# Gate_Driver.net
KiCad netlist of a schematic drawn in Altium Designer
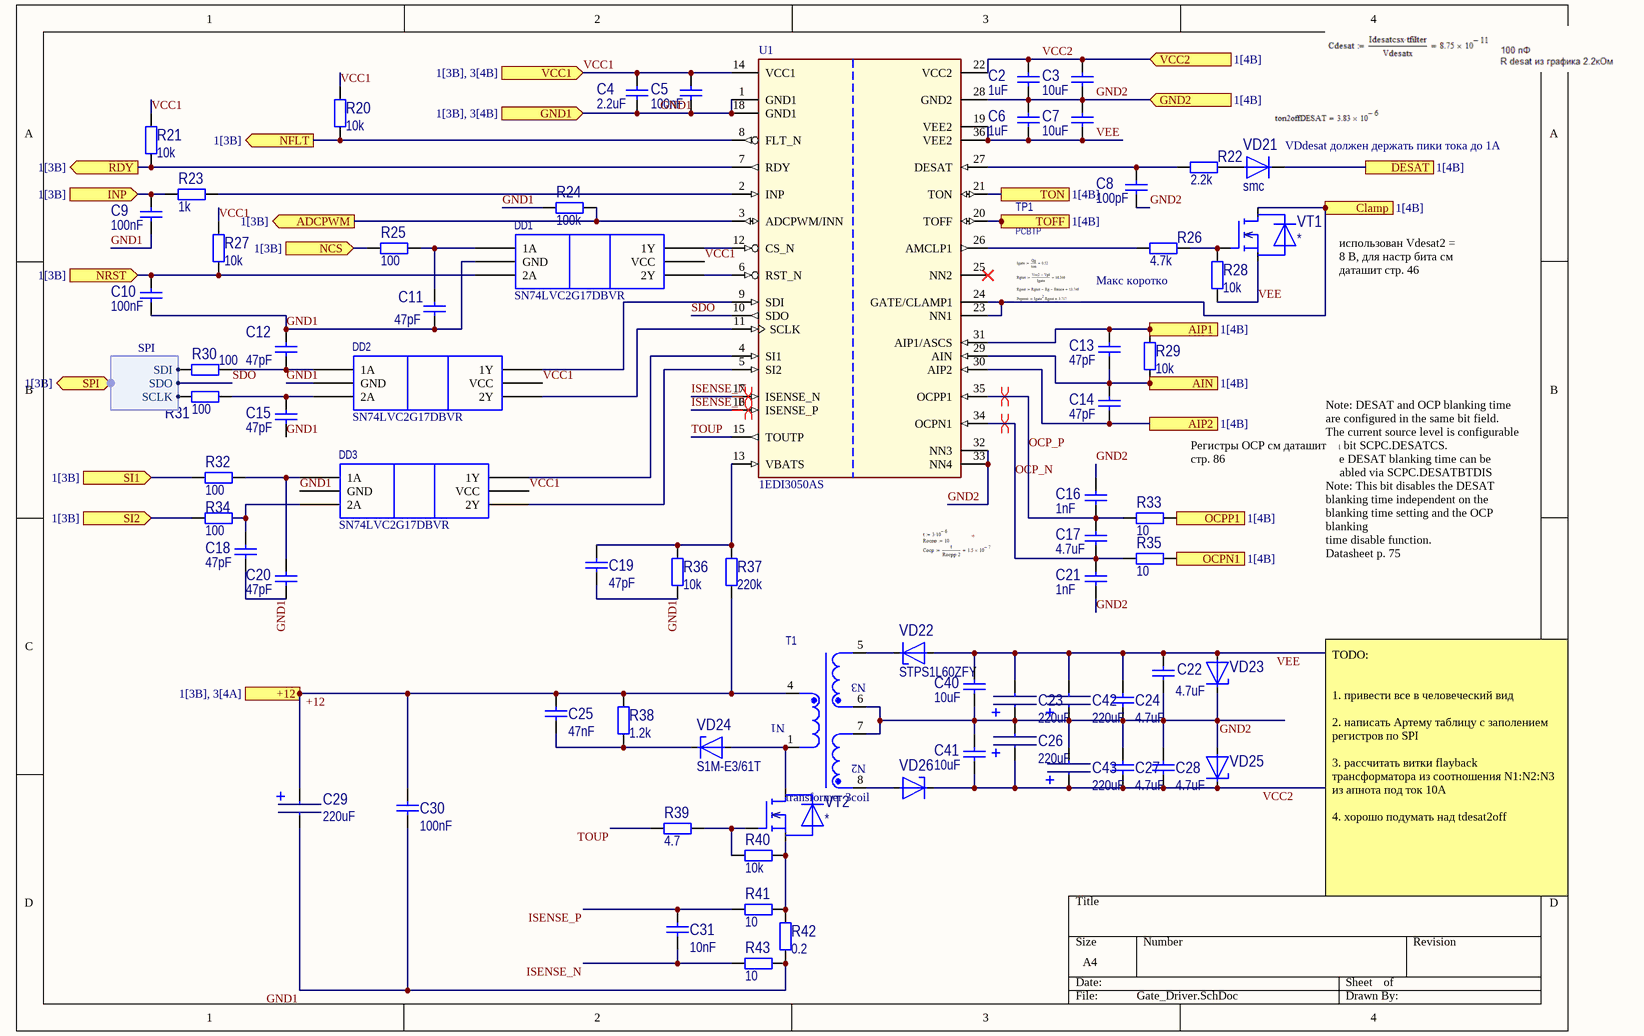
[diagram p0: Gate_Driver.SchDoc]

(export (version "E")
  (design (tool "Eeschema 10.0.6"))
  (components
    (comp (ref "C2")
      (value "1uF")
      (footprint "6332[2512]")
      (description "Конденсатор")
      (fields
        (field (name "MANUFACTURER") "Murata")
        (field (name "MANUFACTURERPARTNUMBER") "GRM21B X7R 104 50V")
      )
      (libsource (lib "Schlibgost") (part "C-4del"))
    )
    (comp (ref "C3")
      (value "10uF")
      (footprint "6332[2512]")
      (description "Конденсатор")
      (fields
        (field (name "MANUFACTURER") "Murata")
        (field (name "MANUFACTURERPARTNUMBER") "GRM21B X7R 104 50V")
      )
      (libsource (lib "Schlibgost") (part "C-4del"))
    )
    (comp (ref "C4")
      (value "2.2uF")
      (footprint "3216[1206]")
      (description "Конденсатор")
      (fields
        (field (name "MANUFACTURER") "Murata")
        (field (name "MANUFACTURERPARTNUMBER") "GRM21B X7R 104 50V")
      )
      (libsource (lib "Schlibgost") (part "C-4del"))
    )
    (comp (ref "C5")
      (value "100nF")
      (footprint "2012[0805]")
      (description "Конденсатор")
      (fields
        (field (name "MANUFACTURER") "Murata")
        (field (name "MANUFACTURERPARTNUMBER") "GRM21B X7R 104 50V")
      )
      (libsource (lib "Schlibgost") (part "C-4del"))
    )
    (comp (ref "C6")
      (value "1uF")
      (footprint "6332[2512]")
      (description "Конденсатор")
      (fields
        (field (name "MANUFACTURER") "Murata")
        (field (name "MANUFACTURERPARTNUMBER") "GRM21B X7R 104 50V")
      )
      (libsource (lib "Schlibgost") (part "C-4del"))
    )
    (comp (ref "C7")
      (value "10uF")
      (footprint "6332[2512]")
      (description "Конденсатор")
      (fields
        (field (name "MANUFACTURER") "Murata")
        (field (name "MANUFACTURERPARTNUMBER") "GRM21B X7R 104 50V")
      )
      (libsource (lib "Schlibgost") (part "C-4del"))
    )
    (comp (ref "C8")
      (value "100pF")
      (footprint "2012[0805]")
      (description "Конденсатор")
      (fields
        (field (name "MANUFACTURER") "Murata")
        (field (name "MANUFACTURERPARTNUMBER") "GRM21B X7R 104 50V")
      )
      (libsource (lib "Schlibgost") (part "C-4del"))
    )
    (comp (ref "C9")
      (value "100nF")
      (footprint "2012[0805]")
      (description "Конденсатор")
      (fields
        (field (name "MANUFACTURER") "Murata")
        (field (name "MANUFACTURERPARTNUMBER") "GRM21B X7R 104 50V")
      )
      (libsource (lib "Schlibgost") (part "C-4del"))
    )
    (comp (ref "C10")
      (value "100nF")
      (footprint "2012[0805]")
      (description "Конденсатор")
      (fields
        (field (name "MANUFACTURER") "Murata")
        (field (name "MANUFACTURERPARTNUMBER") "GRM21B X7R 104 50V")
      )
      (libsource (lib "Schlibgost") (part "C-4del"))
    )
    (comp (ref "C11")
      (value "47pF")
      (footprint "2012[0805]")
      (description "Конденсатор")
      (fields
        (field (name "MANUFACTURER") "Murata")
        (field (name "MANUFACTURERPARTNUMBER") "GRM21B X7R 104 50V")
      )
      (libsource (lib "Schlibgost") (part "C-4del"))
    )
    (comp (ref "C12")
      (value "47pF")
      (footprint "2012[0805]")
      (description "Конденсатор")
      (fields
        (field (name "MANUFACTURER") "Murata")
        (field (name "MANUFACTURERPARTNUMBER") "GRM21B X7R 104 50V")
      )
      (libsource (lib "Schlibgost") (part "C-4del"))
    )
    (comp (ref "C13")
      (value "47pF")
      (footprint "2012[0805]")
      (description "Конденсатор")
      (fields
        (field (name "MANUFACTURER") "Murata")
        (field (name "MANUFACTURERPARTNUMBER") "GRM21B X7R 104 50V")
      )
      (libsource (lib "Schlibgost") (part "C-4del"))
    )
    (comp (ref "C14")
      (value "47pF")
      (footprint "2012[0805]")
      (description "Конденсатор")
      (fields
        (field (name "MANUFACTURER") "Murata")
        (field (name "MANUFACTURERPARTNUMBER") "GRM21B X7R 104 50V")
      )
      (libsource (lib "Schlibgost") (part "C-4del"))
    )
    (comp (ref "C15")
      (value "47pF")
      (footprint "2012[0805]")
      (description "Конденсатор")
      (fields
        (field (name "MANUFACTURER") "Murata")
        (field (name "MANUFACTURERPARTNUMBER") "GRM21B X7R 104 50V")
      )
      (libsource (lib "Schlibgost") (part "C-4del"))
    )
    (comp (ref "C16")
      (value "1nF")
      (footprint "2012[0805]")
      (description "Конденсатор")
      (fields
        (field (name "MANUFACTURER") "Murata")
        (field (name "MANUFACTURERPARTNUMBER") "GRM21B X7R 104 50V")
      )
      (libsource (lib "Schlibgost") (part "C-4del"))
    )
    (comp (ref "C17")
      (value "4.7uF")
      (footprint "2012[0805]")
      (description "Конденсатор")
      (fields
        (field (name "MANUFACTURER") "Murata")
        (field (name "MANUFACTURERPARTNUMBER") "GRM21B X7R 104 50V")
      )
      (libsource (lib "Schlibgost") (part "C-4del"))
    )
    (comp (ref "C18")
      (value "47pF")
      (footprint "2012[0805]")
      (description "Конденсатор")
      (fields
        (field (name "MANUFACTURER") "Murata")
        (field (name "MANUFACTURERPARTNUMBER") "GRM21B X7R 104 50V")
      )
      (libsource (lib "Schlibgost") (part "C-4del"))
    )
    (comp (ref "C19")
      (value "47pF")
      (footprint "2012[0805]")
      (description "Конденсатор")
      (fields
        (field (name "MANUFACTURER") "Murata")
        (field (name "MANUFACTURERPARTNUMBER") "GRM21B X7R 104 50V")
      )
      (libsource (lib "Schlibgost") (part "C-4del"))
    )
    (comp (ref "C20")
      (value "47pF")
      (footprint "2012[0805]")
      (description "Конденсатор")
      (fields
        (field (name "MANUFACTURER") "Murata")
        (field (name "MANUFACTURERPARTNUMBER") "GRM21B X7R 104 50V")
      )
      (libsource (lib "Schlibgost") (part "C-4del"))
    )
    (comp (ref "C21")
      (value "1nF")
      (footprint "2012[0805]")
      (description "Конденсатор")
      (fields
        (field (name "MANUFACTURER") "Murata")
        (field (name "MANUFACTURERPARTNUMBER") "GRM21B X7R 104 50V")
      )
      (libsource (lib "Schlibgost") (part "C-4del"))
    )
    (comp (ref "C22")
      (value "4.7uF")
      (footprint "6332[2512]")
      (description "Конденсатор")
      (fields
        (field (name "MANUFACTURER") "Murata")
        (field (name "MANUFACTURERPARTNUMBER") "GRM21B X7R 104 50V")
      )
      (libsource (lib "Schlibgost") (part "C-4del"))
    )
    (comp (ref "C23")
      (value "220uF")
      (footprint "ECAP 220 50V")
      (description "Конденсатор электролитический")
      (libsource (lib "Schlibgost") (part "C pol"))
    )
    (comp (ref "C24")
      (value "4.7uF")
      (footprint "6332[2512]")
      (description "Конденсатор")
      (fields
        (field (name "MANUFACTURER") "Murata")
        (field (name "MANUFACTURERPARTNUMBER") "GRM21B X7R 104 50V")
      )
      (libsource (lib "Schlibgost") (part "C-4del"))
    )
    (comp (ref "C25")
      (value "47nF")
      (footprint "2012[0805]")
      (description "Конденсатор")
      (fields
        (field (name "MANUFACTURER") "Murata")
        (field (name "MANUFACTURERPARTNUMBER") "GRM21B X7R 104 50V")
      )
      (libsource (lib "Schlibgost") (part "C-4del"))
    )
    (comp (ref "C26")
      (value "220uF")
      (footprint "ECAP 220 50V")
      (description "Конденсатор электролитический")
      (libsource (lib "Schlibgost") (part "C pol"))
    )
    (comp (ref "C27")
      (value "4.7uF")
      (footprint "6332[2512]")
      (description "Конденсатор")
      (fields
        (field (name "MANUFACTURER") "Murata")
        (field (name "MANUFACTURERPARTNUMBER") "GRM21B X7R 104 50V")
      )
      (libsource (lib "Schlibgost") (part "C-4del"))
    )
    (comp (ref "C28")
      (value "4.7uF")
      (footprint "6332[2512]")
      (description "Конденсатор")
      (fields
        (field (name "MANUFACTURER") "Murata")
        (field (name "MANUFACTURERPARTNUMBER") "GRM21B X7R 104 50V")
      )
      (libsource (lib "Schlibgost") (part "C-4del"))
    )
    (comp (ref "C29")
      (value "220uF")
      (footprint "A(3216)")
      (description "Конденсатор электролитический")
      (libsource (lib "Schlibgost") (part "C pol"))
    )
    (comp (ref "C30")
      (value "100nF")
      (footprint "6332[2512]")
      (description "Конденсатор")
      (fields
        (field (name "MANUFACTURER") "Murata")
        (field (name "MANUFACTURERPARTNUMBER") "GRM21B X7R 104 50V")
      )
      (libsource (lib "Schlibgost") (part "C-4del"))
    )
    (comp (ref "C31")
      (value "10nF")
      (footprint "1005[0402]")
      (description "Конденсатор")
      (fields
        (field (name "MANUFACTURER") "Murata")
        (field (name "MANUFACTURERPARTNUMBER") "GRM21B X7R 104 50V")
      )
      (libsource (lib "Schlibgost") (part "C-4del"))
    )
    (comp (ref "C40")
      (value "10uF")
      (footprint "6332[2512]")
      (description "Конденсатор")
      (fields
        (field (name "MANUFACTURER") "Murata")
        (field (name "MANUFACTURERPARTNUMBER") "GRM21B X7R 104 50V")
      )
      (libsource (lib "Schlibgost") (part "C-4del"))
    )
    (comp (ref "C41")
      (value "10uF")
      (footprint "6332[2512]")
      (description "Конденсатор")
      (fields
        (field (name "MANUFACTURER") "Murata")
        (field (name "MANUFACTURERPARTNUMBER") "GRM21B X7R 104 50V")
      )
      (libsource (lib "Schlibgost") (part "C-4del"))
    )
    (comp (ref "C42")
      (value "220uF")
      (footprint "ECAP 220 50V")
      (description "Конденсатор электролитический")
      (libsource (lib "Schlibgost") (part "C pol"))
    )
    (comp (ref "C43")
      (value "220uF")
      (footprint "ECAP 220 50V")
      (description "Конденсатор электролитический")
      (libsource (lib "Schlibgost") (part "C pol"))
    )
    (comp (ref "DD1")
      (value "SN74LVC2G17DBVR")
      (footprint "SOT23-6")
      (libsource (lib "Schlibgost_pn") (part "SN74LVC"))
    )
    (comp (ref "DD2")
      (value "SN74LVC2G17DBVR")
      (footprint "SOT23-6")
      (libsource (lib "Schlibgost_pn") (part "SN74LVC"))
    )
    (comp (ref "DD3")
      (value "SN74LVC2G17DBVR")
      (footprint "SOT23-6")
      (libsource (lib "Schlibgost_pn") (part "SN74LVC"))
    )
    (comp (ref "R20")
      (value "10k")
      (footprint "2012[0805]")
      (description "Резистор")
      (fields (field (name "TOLERANCE") "5%") (field (name "MANUFACTURER") "Yageo"))
      (libsource (lib "") (part "R-4del_2"))
    )
    (comp (ref "R21")
      (value "10k")
      (footprint "2012[0805]")
      (description "Резистор")
      (fields (field (name "TOLERANCE") "5%") (field (name "MANUFACTURER") "Yageo"))
      (libsource (lib "") (part "R-4del_2"))
    )
    (comp (ref "R22")
      (value "2.2k")
      (footprint "3216[1206]")
      (description "Резистор")
      (fields (field (name "TOLERANCE") "5%") (field (name "MANUFACTURER") "Yageo"))
      (libsource (lib "") (part "R-4del_1"))
    )
    (comp (ref "R23")
      (value "1k")
      (footprint "2012[0805]")
      (description "Резистор")
      (fields (field (name "TOLERANCE") "5%") (field (name "MANUFACTURER") "Yageo"))
      (libsource (lib "Schlibgost") (part "R-4del"))
    )
    (comp (ref "R24")
      (value "100k")
      (footprint "1005[0402]")
      (description "Резистор")
      (fields (field (name "TOLERANCE") "5%") (field (name "MANUFACTURER") "Yageo"))
      (libsource (lib "Schlibgost") (part "R-4del"))
    )
    (comp (ref "R25")
      (value "100")
      (footprint "2012[0805]")
      (description "Резистор")
      (fields (field (name "TOLERANCE") "5%") (field (name "MANUFACTURER") "Yageo"))
      (libsource (lib "Schlibgost") (part "R-4del"))
    )
    (comp (ref "R26")
      (value "4.7k")
      (footprint "2012[0805]")
      (description "Резистор")
      (fields (field (name "TOLERANCE") "5%") (field (name "MANUFACTURER") "Yageo"))
      (libsource (lib "") (part "R-4del_1"))
    )
    (comp (ref "R27")
      (value "10k")
      (footprint "2012[0805]")
      (description "Резистор")
      (fields (field (name "TOLERANCE") "5%") (field (name "MANUFACTURER") "Yageo"))
      (libsource (lib "") (part "R-4del_2"))
    )
    (comp (ref "R28")
      (value "10k")
      (footprint "2012[0805]")
      (description "Резистор")
      (fields (field (name "TOLERANCE") "5%") (field (name "MANUFACTURER") "Yageo"))
      (libsource (lib "") (part "R-4del_2"))
    )
    (comp (ref "R29")
      (value "10k")
      (footprint "2012[0805]")
      (description "Резистор")
      (fields (field (name "TOLERANCE") "5%") (field (name "MANUFACTURER") "Yageo"))
      (libsource (lib "") (part "R-4del_2"))
    )
    (comp (ref "R30")
      (value "100")
      (footprint "2012[0805]")
      (description "Резистор")
      (fields (field (name "TOLERANCE") "5%") (field (name "MANUFACTURER") "Yageo"))
      (libsource (lib "Schlibgost") (part "R-4del"))
    )
    (comp (ref "R31")
      (value "100")
      (footprint "2012[0805]")
      (description "Резистор")
      (fields (field (name "TOLERANCE") "5%") (field (name "MANUFACTURER") "Yageo"))
      (libsource (lib "Schlibgost") (part "R-4del"))
    )
    (comp (ref "R32")
      (value "100")
      (footprint "2012[0805]")
      (description "Резистор")
      (fields (field (name "TOLERANCE") "5%") (field (name "MANUFACTURER") "Yageo"))
      (libsource (lib "Schlibgost") (part "R-4del"))
    )
    (comp (ref "R33")
      (value "10")
      (footprint "2012[0805]")
      (description "Резистор")
      (fields (field (name "TOLERANCE") "5%") (field (name "MANUFACTURER") "Yageo"))
      (libsource (lib "Schlibgost") (part "R-4del"))
    )
    (comp (ref "R34")
      (value "100")
      (footprint "2012[0805]")
      (description "Резистор")
      (fields (field (name "TOLERANCE") "5%") (field (name "MANUFACTURER") "Yageo"))
      (libsource (lib "Schlibgost") (part "R-4del"))
    )
    (comp (ref "R35")
      (value "10")
      (footprint "2012[0805]")
      (description "Резистор")
      (fields (field (name "TOLERANCE") "5%") (field (name "MANUFACTURER") "Yageo"))
      (libsource (lib "Schlibgost") (part "R-4del"))
    )
    (comp (ref "R36")
      (value "10k")
      (footprint "2012[0805]")
      (description "Резистор")
      (fields (field (name "TOLERANCE") "5%") (field (name "MANUFACTURER") "Yageo"))
      (libsource (lib "") (part "R-4del_2"))
    )
    (comp (ref "R37")
      (value "220k")
      (footprint "2012[0805]")
      (description "Резистор")
      (fields (field (name "TOLERANCE") "5%") (field (name "MANUFACTURER") "Yageo"))
      (libsource (lib "") (part "R-4del_2"))
    )
    (comp (ref "R38")
      (value "1.2k")
      (footprint "2012[0805]")
      (description "Резистор")
      (fields (field (name "TOLERANCE") "5%") (field (name "MANUFACTURER") "Yageo"))
      (libsource (lib "") (part "R-4del_2"))
    )
    (comp (ref "R39")
      (value "4.7")
      (footprint "2012[0805]")
      (description "Резистор")
      (fields (field (name "TOLERANCE") "5%") (field (name "MANUFACTURER") "Yageo"))
      (libsource (lib "") (part "R-4del_1"))
    )
    (comp (ref "R40")
      (value "10k")
      (footprint "2012[0805]")
      (description "Резистор")
      (fields (field (name "TOLERANCE") "5%") (field (name "MANUFACTURER") "Yageo"))
      (libsource (lib "Schlibgost") (part "R-4del"))
    )
    (comp (ref "R41")
      (value "10")
      (footprint "2012[0805]")
      (description "Резистор")
      (fields (field (name "TOLERANCE") "5%") (field (name "MANUFACTURER") "Yageo"))
      (libsource (lib "Schlibgost") (part "R-4del"))
    )
    (comp (ref "R42")
      (value "0.2")
      (footprint "2512")
      (description "Резистор")
      (fields (field (name "TOLERANCE") "5%") (field (name "MANUFACTURER") "Yageo"))
      (libsource (lib "") (part "R-4del_3"))
    )
    (comp (ref "R43")
      (value "10")
      (footprint "2012[0805]")
      (description "Резистор")
      (fields (field (name "TOLERANCE") "5%") (field (name "MANUFACTURER") "Yageo"))
      (libsource (lib "Schlibgost") (part "R-4del"))
    )
    (comp (ref "T1")
      (value "transformer 3coil")
      (footprint "E 13/7/4")
      (libsource (lib "Schlibgost") (part "transformer 3coil"))
    )
    (comp (ref "TP1") (value "PCBTP") (libsource (lib "Schlibgost") (part "Testpoint")))
    (comp (ref "U1")
      (value "1EDI3050AS")
      (description "Single channel isolated IGBT/SiC-MOSFET driver")
      (fields (field (name "MANUFACTURER") "Infineon Technologies"))
      (libsource (lib "1EDI3050AS") (part "1EDI3050AS"))
    )
    (comp (ref "VD21")
      (value "smc")
      (footprint "SMС")
      (description "Диод")
      (libsource (lib "Schlibgost") (part "VD Diod"))
    )
    (comp (ref "VD22")
      (value "STPS1L60ZFY")
      (footprint "SOD-123")
      (description "Стабилитрон односторонний")
      (libsource (lib "Schlibgost") (part "VD Stabilitron"))
    )
    (comp (ref "VD23")
      (value "~")
      (footprint "SMС")
      (description "Стабилитрон односторонний")
      (libsource (lib "Schlibgost") (part "VD Stabilitron"))
    )
    (comp (ref "VD24")
      (value "S1M-E3/61T")
      (footprint "SMB")
      (description "Стабилитрон односторонний")
      (libsource (lib "Schlibgost") (part "VD Stabilitron"))
    )
    (comp (ref "VD25")
      (value "~")
      (footprint "SMС")
      (description "Стабилитрон односторонний")
      (libsource (lib "Schlibgost") (part "VD Stabilitron"))
    )
    (comp (ref "VD26")
      (value "~")
      (footprint "SOD-123")
      (description "Стабилитрон односторонний")
      (libsource (lib "Schlibgost") (part "VD Stabilitron"))
    )
    (comp (ref "VT1")
      (value "*")
      (description "Транзистор полевой n-канальный")
      (libsource (lib "Schlibgost") (part "VT Transistor NMOS+D"))
    )
    (comp (ref "VT2")
      (value "*")
      (description "Транзистор полевой n-канальный")
      (libsource (lib "Schlibgost") (part "VT Transistor NMOS+D"))
    )
  )
  (nets
    (net (code "2") (name "/+12") (class "Default")
      (node (ref "C25") (pin "1") (pinfunction "1_1") (pintype "passive"))
      (node (ref "C29") (pin "1") (pinfunction "1_1") (pintype "passive"))
      (node (ref "C30") (pin "1") (pinfunction "1_1") (pintype "passive"))
      (node (ref "R37") (pin "1") (pinfunction "1_1") (pintype "passive"))
      (node (ref "R38") (pin "2") (pinfunction "2_2") (pintype "passive"))
      (node (ref "T1") (pin "4") (pinfunction "4_4") (pintype "passive"))
    )
    (net (code "3") (name "/ADCPWM") (class "Default")
      (node (ref "R24") (pin "1") (pinfunction "1_1") (pintype "passive"))
      (node (ref "U1") (pin "3") (pinfunction "ADCPWM/INN_3") (pintype "bidirectional"))
    )
    (net (code "4") (name "/AIN") (class "Default")
      (node (ref "C13") (pin "2") (pinfunction "2_2") (pintype "passive"))
      (node (ref "C14") (pin "1") (pinfunction "1_1") (pintype "passive"))
      (node (ref "R29") (pin "1") (pinfunction "1_1") (pintype "passive"))
      (node (ref "U1") (pin "29") (pinfunction "AIN_29") (pintype "input"))
    )
    (net (code "5") (name "/AIP1") (class "Default")
      (node (ref "C13") (pin "1") (pinfunction "1_1") (pintype "passive"))
      (node (ref "R29") (pin "2") (pinfunction "2_2") (pintype "passive"))
      (node (ref "U1") (pin "31") (pinfunction "AIP1/ASCS_31") (pintype "input"))
    )
    (net (code "6") (name "/AIP2") (class "Default")
      (node (ref "C14") (pin "2") (pinfunction "2_2") (pintype "passive"))
      (node (ref "U1") (pin "30") (pinfunction "AIP2_30") (pintype "input"))
    )
    (net (code "7") (name "/Clamp") (class "Default")
      (node (ref "U1") (pin "23") (pinfunction "NN1_23") (pintype "passive"))
      (node (ref "U1") (pin "24") (pinfunction "GATE/CLAMP1_24") (pintype "power_in"))
      (node (ref "VT1") (pin "1") (pinfunction "D_1") (pintype "passive"))
    )
    (net (code "8") (name "/DESAT") (class "Default")
      (node (ref "VD21") (pin "2") (pinfunction "K_2") (pintype "passive"))
    )
    (net (code "9") (name "/GND1") (class "Default")
      (node (ref "C10") (pin "2") (pinfunction "2_2") (pintype "passive"))
      (node (ref "C11") (pin "2") (pinfunction "2_2") (pintype "passive"))
      (node (ref "C12") (pin "1") (pinfunction "1_1") (pintype "passive"))
      (node (ref "C15") (pin "2") (pinfunction "2_2") (pintype "passive"))
      (node (ref "C18") (pin "2") (pinfunction "2_2") (pintype "passive"))
      (node (ref "C19") (pin "2") (pinfunction "2_2") (pintype "passive"))
      (node (ref "C20") (pin "2") (pinfunction "2_2") (pintype "passive"))
      (node (ref "C29") (pin "2") (pinfunction "2_2") (pintype "passive"))
      (node (ref "C30") (pin "2") (pinfunction "2_2") (pintype "passive"))
      (node (ref "C4") (pin "2") (pinfunction "2_2") (pintype "passive"))
      (node (ref "C5") (pin "2") (pinfunction "2_2") (pintype "passive"))
      (node (ref "C9") (pin "2") (pinfunction "2_2") (pintype "passive"))
      (node (ref "DD1") (pin "2") (pinfunction "GND_2") (pintype "passive"))
      (node (ref "DD2") (pin "2") (pinfunction "GND_2") (pintype "passive"))
      (node (ref "DD3") (pin "2") (pinfunction "GND_2") (pintype "passive"))
      (node (ref "R24") (pin "2") (pinfunction "2_2") (pintype "passive"))
      (node (ref "R36") (pin "1") (pinfunction "1_1") (pintype "passive"))
      (node (ref "R42") (pin "2") (pinfunction "2_2") (pintype "passive"))
      (node (ref "R43") (pin "1") (pinfunction "1_1") (pintype "passive"))
      (node (ref "U1") (pin "1") (pinfunction "GND1_1") (pintype "power_in"))
      (node (ref "U1") (pin "18") (pinfunction "GND1_18") (pintype "power_in"))
    )
    (net (code "10") (name "/GND2") (class "Default")
      (node (ref "C16") (pin "1") (pinfunction "1_1") (pintype "passive"))
      (node (ref "C2") (pin "2") (pinfunction "2_2") (pintype "passive"))
      (node (ref "C21") (pin "2") (pinfunction "2_2") (pintype "passive"))
      (node (ref "C22") (pin "1") (pinfunction "1_1") (pintype "passive"))
      (node (ref "C23") (pin "1") (pinfunction "1_1") (pintype "passive"))
      (node (ref "C24") (pin "1") (pinfunction "1_1") (pintype "passive"))
      (node (ref "C26") (pin "2") (pinfunction "2_2") (pintype "passive"))
      (node (ref "C27") (pin "2") (pinfunction "2_2") (pintype "passive"))
      (node (ref "C28") (pin "2") (pinfunction "2_2") (pintype "passive"))
      (node (ref "C3") (pin "2") (pinfunction "2_2") (pintype "passive"))
      (node (ref "C40") (pin "2") (pinfunction "2_2") (pintype "passive"))
      (node (ref "C41") (pin "1") (pinfunction "1_1") (pintype "passive"))
      (node (ref "C42") (pin "1") (pinfunction "1_1") (pintype "passive"))
      (node (ref "C43") (pin "2") (pinfunction "2_2") (pintype "passive"))
      (node (ref "C6") (pin "1") (pinfunction "1_1") (pintype "passive"))
      (node (ref "C7") (pin "1") (pinfunction "1_1") (pintype "passive"))
      (node (ref "C8") (pin "2") (pinfunction "2_2") (pintype "passive"))
      (node (ref "T1") (pin "6") (pinfunction "6_6") (pintype "passive"))
      (node (ref "T1") (pin "7") (pinfunction "7_7") (pintype "passive"))
      (node (ref "U1") (pin "28") (pinfunction "GND2_28") (pintype "power_in"))
      (node (ref "U1") (pin "32") (pinfunction "NN3_32") (pintype "passive"))
      (node (ref "U1") (pin "33") (pinfunction "NN4_33") (pintype "passive"))
      (node (ref "VD23") (pin "2") (pinfunction "K_2") (pintype "passive"))
      (node (ref "VD25") (pin "1") (pinfunction "A_1") (pintype "passive"))
    )
    (net (code "11") (name "/INP") (class "Default")
      (node (ref "C9") (pin "1") (pinfunction "1_1") (pintype "passive"))
      (node (ref "R23") (pin "2") (pinfunction "2_2") (pintype "passive"))
    )
    (net (code "12") (name "/ISENSE_N") (class "Default")
      (node (ref "C31") (pin "2") (pinfunction "2_2") (pintype "passive"))
      (node (ref "R43") (pin "2") (pinfunction "2_2") (pintype "passive"))
      (node (ref "U1") (pin "17") (pinfunction "ISENSE_N_17") (pintype "input"))
    )
    (net (code "13") (name "/ISENSE_P") (class "Default")
      (node (ref "C31") (pin "1") (pinfunction "1_1") (pintype "passive"))
      (node (ref "R41") (pin "2") (pinfunction "2_2") (pintype "passive"))
      (node (ref "U1") (pin "16") (pinfunction "ISENSE_P_16") (pintype "input"))
    )
    (net (code "14") (name "/NCS") (class "Default")
      (node (ref "R25") (pin "2") (pinfunction "2_2") (pintype "passive"))
    )
    (net (code "15") (name "/NFLT") (class "Default")
      (node (ref "R20") (pin "1") (pinfunction "1_1") (pintype "passive"))
      (node (ref "U1") (pin "8") (pinfunction "FLT_N_8") (pintype "output"))
    )
    (net (code "16") (name "/NRST") (class "Default")
      (node (ref "C10") (pin "1") (pinfunction "1_1") (pintype "passive"))
      (node (ref "DD1") (pin "3") (pinfunction "2A_3") (pintype "passive"))
      (node (ref "R27") (pin "1") (pinfunction "1_1") (pintype "passive"))
    )
    (net (code "17") (name "/OCPN1") (class "Default")
      (node (ref "R35") (pin "1") (pinfunction "1_1") (pintype "passive"))
    )
    (net (code "18") (name "/OCPP1") (class "Default")
      (node (ref "R33") (pin "1") (pinfunction "1_1") (pintype "passive"))
    )
    (net (code "19") (name "/OCP_N") (class "Default")
      (node (ref "C17") (pin "2") (pinfunction "2_2") (pintype "passive"))
      (node (ref "C21") (pin "1") (pinfunction "1_1") (pintype "passive"))
      (node (ref "R35") (pin "2") (pinfunction "2_2") (pintype "passive"))
      (node (ref "U1") (pin "34") (pinfunction "OCPN1_34") (pintype "input"))
    )
    (net (code "20") (name "/OCP_P") (class "Default")
      (node (ref "C16") (pin "2") (pinfunction "2_2") (pintype "passive"))
      (node (ref "C17") (pin "1") (pinfunction "1_1") (pintype "passive"))
      (node (ref "R33") (pin "2") (pinfunction "2_2") (pintype "passive"))
      (node (ref "U1") (pin "35") (pinfunction "OCPP1_35") (pintype "input"))
    )
    (net (code "21") (name "/RDY") (class "Default")
      (node (ref "R21") (pin "1") (pinfunction "1_1") (pintype "passive"))
      (node (ref "U1") (pin "7") (pinfunction "RDY_7") (pintype "output"))
    )
    (net (code "22") (name "/SCLK") (class "Default")
      (node (ref "R31") (pin "2") (pinfunction "2_2") (pintype "passive"))
    )
    (net (code "23") (name "/SDI") (class "Default")
      (node (ref "R30") (pin "2") (pinfunction "2_2") (pintype "passive"))
    )
    (net (code "24") (name "/SDO") (class "Default")
      (node (ref "U1") (pin "10") (pinfunction "SDO_10") (pintype "output"))
    )
    (net (code "25") (name "/SI1") (class "Default")
      (node (ref "R32") (pin "2") (pinfunction "2_2") (pintype "passive"))
    )
    (net (code "26") (name "/SI2") (class "Default")
      (node (ref "R34") (pin "2") (pinfunction "2_2") (pintype "passive"))
    )
    (net (code "27") (name "/TOFF") (class "Default")
      (node (ref "TP1") (pin "1") (pinfunction "1_1") (pintype "passive"))
      (node (ref "U1") (pin "20") (pinfunction "TOFF_20") (pintype "bidirectional"))
    )
    (net (code "28") (name "/TON") (class "Default")
      (node (ref "U1") (pin "21") (pinfunction "TON_21") (pintype "bidirectional"))
    )
    (net (code "29") (name "/TOUP") (class "Default")
      (node (ref "R39") (pin "1") (pinfunction "1_1") (pintype "passive"))
      (node (ref "U1") (pin "15") (pinfunction "TOUTP_15") (pintype "output"))
    )
    (net (code "30") (name "/VCC1") (class "Default")
      (node (ref "C4") (pin "1") (pinfunction "1_1") (pintype "passive"))
      (node (ref "C5") (pin "1") (pinfunction "1_1") (pintype "passive"))
      (node (ref "DD1") (pin "5") (pinfunction "VCC_5") (pintype "passive"))
      (node (ref "DD2") (pin "5") (pinfunction "VCC_5") (pintype "passive"))
      (node (ref "DD3") (pin "5") (pinfunction "VCC_5") (pintype "passive"))
      (node (ref "R20") (pin "2") (pinfunction "2_2") (pintype "passive"))
      (node (ref "R21") (pin "2") (pinfunction "2_2") (pintype "passive"))
      (node (ref "R27") (pin "2") (pinfunction "2_2") (pintype "passive"))
      (node (ref "U1") (pin "14") (pinfunction "VCC1_14") (pintype "power_in"))
    )
    (net (code "31") (name "/VCC2") (class "Default")
      (node (ref "C2") (pin "1") (pinfunction "1_1") (pintype "passive"))
      (node (ref "C26") (pin "1") (pinfunction "1_1") (pintype "passive"))
      (node (ref "C27") (pin "1") (pinfunction "1_1") (pintype "passive"))
      (node (ref "C28") (pin "1") (pinfunction "1_1") (pintype "passive"))
      (node (ref "C3") (pin "1") (pinfunction "1_1") (pintype "passive"))
      (node (ref "C41") (pin "2") (pinfunction "2_2") (pintype "passive"))
      (node (ref "C43") (pin "1") (pinfunction "1_1") (pintype "passive"))
      (node (ref "U1") (pin "22") (pinfunction "VCC2_22") (pintype "power_in"))
      (node (ref "VD25") (pin "2") (pinfunction "K_2") (pintype "passive"))
      (node (ref "VD26") (pin "2") (pinfunction "K_2") (pintype "passive"))
    )
    (net (code "32") (name "/VEE") (class "Default")
      (node (ref "C22") (pin "2") (pinfunction "2_2") (pintype "passive"))
      (node (ref "C23") (pin "2") (pinfunction "2_2") (pintype "passive"))
      (node (ref "C24") (pin "2") (pinfunction "2_2") (pintype "passive"))
      (node (ref "C40") (pin "1") (pinfunction "1_1") (pintype "passive"))
      (node (ref "C42") (pin "2") (pinfunction "2_2") (pintype "passive"))
      (node (ref "C6") (pin "2") (pinfunction "2_2") (pintype "passive"))
      (node (ref "C7") (pin "2") (pinfunction "2_2") (pintype "passive"))
      (node (ref "R28") (pin "1") (pinfunction "1_1") (pintype "passive"))
      (node (ref "U1") (pin "19") (pinfunction "VEE2_19") (pintype "power_in"))
      (node (ref "U1") (pin "36") (pinfunction "VEE2_36") (pintype "power_in"))
      (node (ref "VD22") (pin "1") (pinfunction "A_1") (pintype "passive"))
      (node (ref "VD23") (pin "1") (pinfunction "A_1") (pintype "passive"))
      (node (ref "VT1") (pin "3") (pinfunction "S_3") (pintype "passive"))
    )
    (net (code "34") (name "Net-(DD1-1A)") (class "Default")
      (node (ref "C11") (pin "1") (pinfunction "1_1") (pintype "passive"))
      (node (ref "DD1") (pin "1") (pinfunction "1A_1") (pintype "passive"))
      (node (ref "R25") (pin "1") (pinfunction "1_1") (pintype "passive"))
    )
    (net (code "35") (name "Net-(DD1-1Y)") (class "Default")
      (node (ref "DD1") (pin "6") (pinfunction "1Y_6") (pintype "passive"))
      (node (ref "U1") (pin "12") (pinfunction "CS_N_12") (pintype "input"))
    )
    (net (code "36") (name "Net-(DD1-2Y)") (class "Default")
      (node (ref "DD1") (pin "4") (pinfunction "2Y_4") (pintype "passive"))
      (node (ref "U1") (pin "6") (pinfunction "RST_N_6") (pintype "input"))
    )
    (net (code "37") (name "Net-(DD2-1A)") (class "Default")
      (node (ref "C12") (pin "2") (pinfunction "2_2") (pintype "passive"))
      (node (ref "DD2") (pin "1") (pinfunction "1A_1") (pintype "passive"))
      (node (ref "R30") (pin "1") (pinfunction "1_1") (pintype "passive"))
    )
    (net (code "38") (name "Net-(DD2-1Y)") (class "Default")
      (node (ref "DD2") (pin "6") (pinfunction "1Y_6") (pintype "passive"))
      (node (ref "U1") (pin "9") (pinfunction "SDI_9") (pintype "input"))
    )
    (net (code "39") (name "Net-(DD2-2A)") (class "Default")
      (node (ref "C15") (pin "1") (pinfunction "1_1") (pintype "passive"))
      (node (ref "DD2") (pin "3") (pinfunction "2A_3") (pintype "passive"))
      (node (ref "R31") (pin "1") (pinfunction "1_1") (pintype "passive"))
    )
    (net (code "40") (name "Net-(DD2-2Y)") (class "Default")
      (node (ref "DD2") (pin "4") (pinfunction "2Y_4") (pintype "passive"))
      (node (ref "U1") (pin "11") (pinfunction "SCLK_11") (pintype "input"))
    )
    (net (code "41") (name "Net-(DD3-1A)") (class "Default")
      (node (ref "C20") (pin "1") (pinfunction "1_1") (pintype "passive"))
      (node (ref "DD3") (pin "1") (pinfunction "1A_1") (pintype "passive"))
      (node (ref "R32") (pin "1") (pinfunction "1_1") (pintype "passive"))
    )
    (net (code "42") (name "Net-(DD3-1Y)") (class "Default")
      (node (ref "DD3") (pin "6") (pinfunction "1Y_6") (pintype "passive"))
      (node (ref "U1") (pin "4") (pinfunction "SI1_4") (pintype "input"))
    )
    (net (code "43") (name "Net-(DD3-2A)") (class "Default")
      (node (ref "C18") (pin "1") (pinfunction "1_1") (pintype "passive"))
      (node (ref "DD3") (pin "3") (pinfunction "2A_3") (pintype "passive"))
      (node (ref "R34") (pin "1") (pinfunction "1_1") (pintype "passive"))
    )
    (net (code "44") (name "Net-(DD3-2Y)") (class "Default")
      (node (ref "DD3") (pin "4") (pinfunction "2Y_4") (pintype "passive"))
      (node (ref "U1") (pin "5") (pinfunction "SI2_5") (pintype "input"))
    )
    (net (code "45") (name "Net-(U1-AMCLP1)") (class "Default")
      (node (ref "R26") (pin "1") (pinfunction "1_1") (pintype "passive"))
      (node (ref "U1") (pin "26") (pinfunction "AMCLP1_26") (pintype "output"))
    )
    (net (code "46") (name "Net-(U1-DESAT)") (class "Default")
      (node (ref "C8") (pin "1") (pinfunction "1_1") (pintype "passive"))
      (node (ref "R22") (pin "1") (pinfunction "1_1") (pintype "passive"))
      (node (ref "U1") (pin "27") (pinfunction "DESAT_27") (pintype "input"))
    )
    (net (code "47") (name "Net-(U1-INP)") (class "Default")
      (node (ref "R23") (pin "1") (pinfunction "1_1") (pintype "passive"))
      (node (ref "U1") (pin "2") (pinfunction "INP_2") (pintype "input"))
    )
    (net (code "48") (name "Net-(U1-VBATS)") (class "Default")
      (node (ref "C19") (pin "1") (pinfunction "1_1") (pintype "passive"))
      (node (ref "R36") (pin "2") (pinfunction "2_2") (pintype "passive"))
      (node (ref "R37") (pin "2") (pinfunction "2_2") (pintype "passive"))
      (node (ref "U1") (pin "13") (pinfunction "VBATS_13") (pintype "input"))
    )
    (net (code "49") (name "Net-(VD21-A)") (class "Default")
      (node (ref "R22") (pin "2") (pinfunction "2_2") (pintype "passive"))
      (node (ref "VD21") (pin "1") (pinfunction "A_1") (pintype "passive"))
    )
    (net (code "50") (name "Net-(VD22-K)") (class "Default")
      (node (ref "T1") (pin "5") (pinfunction "5_5") (pintype "passive"))
      (node (ref "VD22") (pin "2") (pinfunction "K_2") (pintype "passive"))
    )
    (net (code "51") (name "Net-(VD24-A)") (class "Default")
      (node (ref "T1") (pin "1") (pinfunction "1_1") (pintype "passive"))
      (node (ref "VD24") (pin "1") (pinfunction "A_1") (pintype "passive"))
      (node (ref "VT2") (pin "1") (pinfunction "D_1") (pintype "passive"))
    )
    (net (code "52") (name "Net-(VD24-K)") (class "Default")
      (node (ref "C25") (pin "2") (pinfunction "2_2") (pintype "passive"))
      (node (ref "R38") (pin "1") (pinfunction "1_1") (pintype "passive"))
      (node (ref "VD24") (pin "2") (pinfunction "K_2") (pintype "passive"))
    )
    (net (code "53") (name "Net-(VD26-A)") (class "Default")
      (node (ref "T1") (pin "8") (pinfunction "8_8") (pintype "passive"))
      (node (ref "VD26") (pin "1") (pinfunction "A_1") (pintype "passive"))
    )
    (net (code "54") (name "Net-(VT1-G)") (class "Default")
      (node (ref "R26") (pin "2") (pinfunction "2_2") (pintype "passive"))
      (node (ref "R28") (pin "2") (pinfunction "2_2") (pintype "passive"))
      (node (ref "VT1") (pin "2") (pinfunction "G_2") (pintype "passive"))
    )
    (net (code "55") (name "Net-(VT2-G)") (class "Default")
      (node (ref "R39") (pin "2") (pinfunction "2_2") (pintype "passive"))
      (node (ref "R40") (pin "2") (pinfunction "2_2") (pintype "passive"))
      (node (ref "VT2") (pin "2") (pinfunction "G_2") (pintype "passive"))
    )
    (net (code "56") (name "Net-(VT2-S)") (class "Default")
      (node (ref "R40") (pin "1") (pinfunction "1_1") (pintype "passive"))
      (node (ref "R41") (pin "1") (pinfunction "1_1") (pintype "passive"))
      (node (ref "R42") (pin "1") (pinfunction "1_1") (pintype "passive"))
      (node (ref "VT2") (pin "3") (pinfunction "S_3") (pintype "passive"))
    )
    (net (code "57") (name "unconnected-(U1-NN2-Pad25)") (class "Default")
      (node (ref "U1") (pin "25") (pinfunction "NN2_25") (pintype "passive+no_connect"))
    )
  )
)
